# digital_clock_run4a.net
KiCad netlist of a schematic drawn in EasyEDA
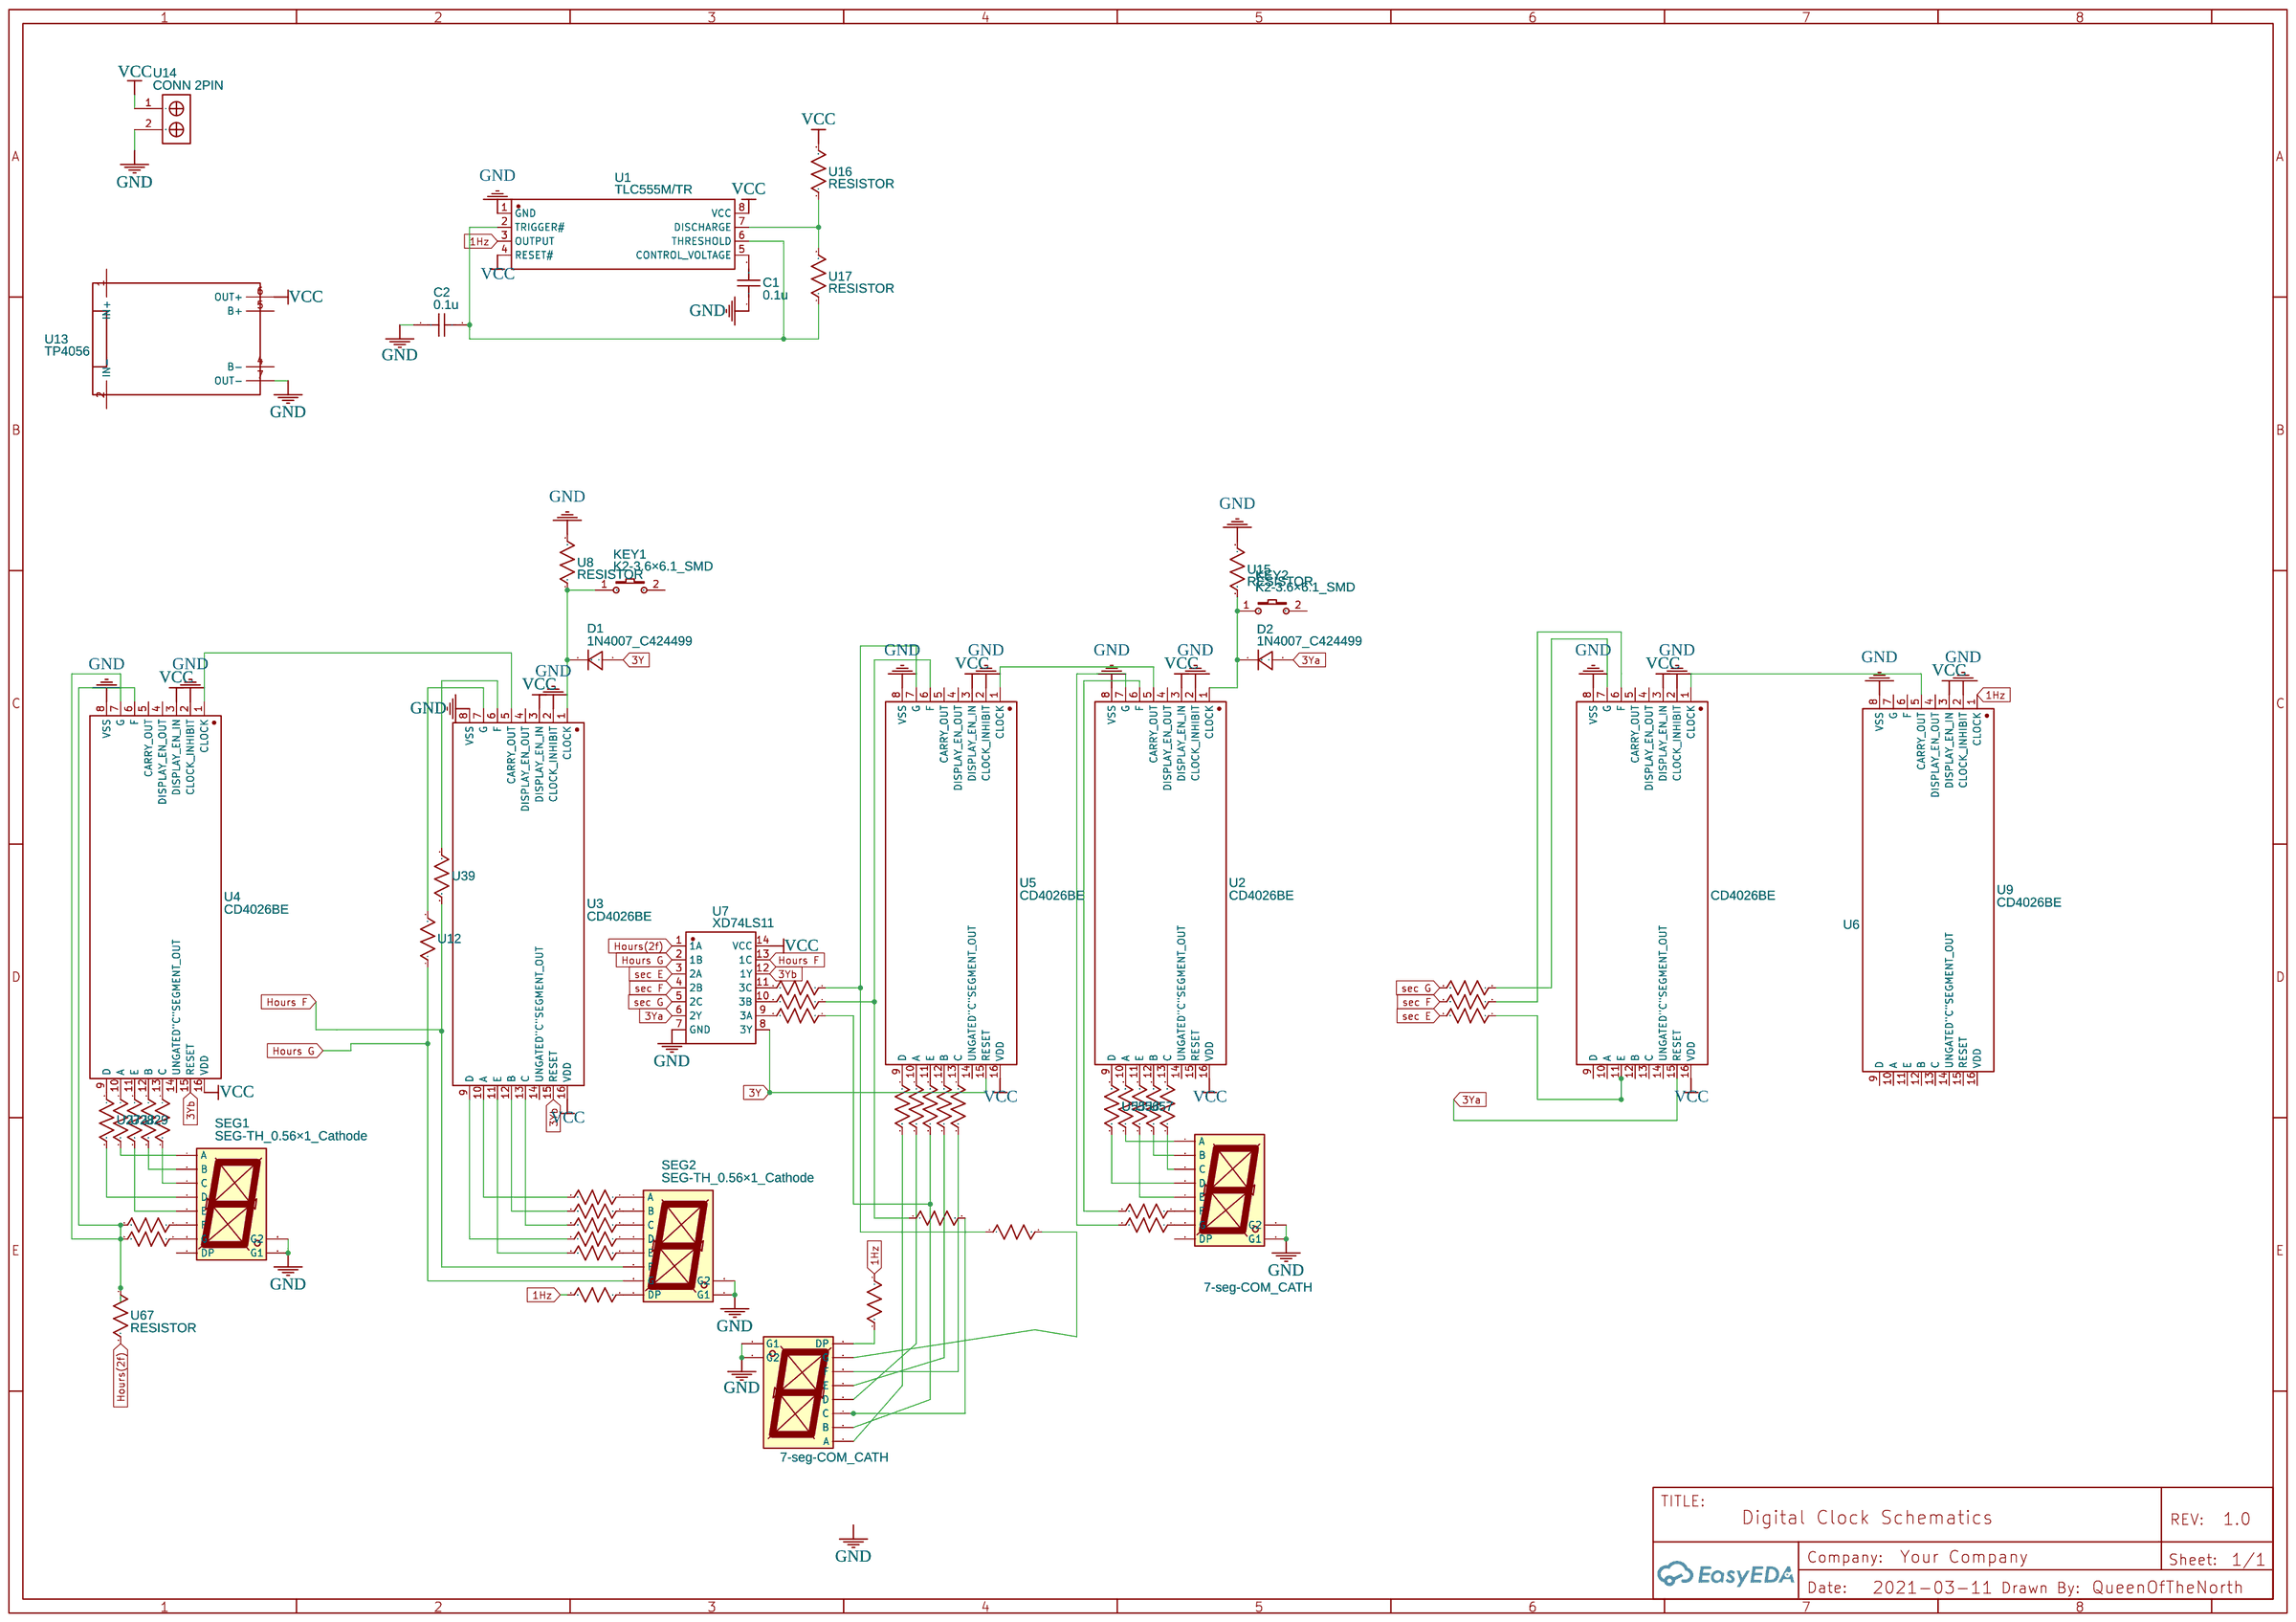
[diagram p0: schematic sheet]

(export (version "E")
  (design (tool "Eeschema 10.0.6"))
  (components
    (comp (ref "C1") (value "0.1u") (libsource (lib "") (part "C_0603_US_1")))
    (comp (ref "C2") (value "0.1u") (libsource (lib "") (part "C_0603_US")))
    (comp (ref "D1")
      (value "1N4007_C424499")
      (fields (field (name "BOM_Manufacturer Part") "1N4007") (field (name "BOM_Supplier Part") "C424499"))
      (libsource (lib "") (part "1N4007_C424499"))
    )
    (comp (ref "D2")
      (value "1N4007_C424499")
      (fields (field (name "BOM_Manufacturer Part") "1N4007") (field (name "BOM_Supplier Part") "C424499"))
      (libsource (lib "") (part "1N4007_C424499"))
    )
    (comp (ref "KEY1")
      (value "K2-3.6×6.1_SMD")
      (fields
        (field (name "BOM_Manufacturer Part") "K2-1107ST-A4SW-06")
        (field (name "BOM_Supplier Part") "C118141")
      )
      (libsource (lib "") (part "K2-3.6×6.1_SMD"))
    )
    (comp (ref "KEY2")
      (value "K2-3.6×6.1_SMD")
      (fields
        (field (name "BOM_Manufacturer Part") "K2-1107ST-A4SW-06")
        (field (name "BOM_Supplier Part") "C118141")
      )
      (libsource (lib "") (part "K2-3.6×6.1_SMD"))
    )
    (comp (ref "SEG1")
      (value "SEG-TH_0.56×1_Cathode")
      (fields (field (name "BOM_Supplier Part") "C8093"))
      (libsource (lib "") (part "SEG-TH_0.56×1_Cathode"))
    )
    (comp (ref "SEG2")
      (value "SEG-TH_0.56×1_Cathode")
      (fields (field (name "BOM_Supplier Part") "C8093"))
      (libsource (lib "") (part "SEG-TH_0.56×1_Cathode"))
    )
    (comp (ref "SEG3")
      (value "7-seg-COM_CATH")
      (fields (field (name "BOM_Supplier Part") "C8093"))
      (libsource (lib "") (part "SEG-TH_0.56×1_Cathode_1"))
    )
    (comp (ref "SEG4")
      (value "7-seg-COM_CATH")
      (fields (field (name "BOM_Supplier Part") "C8093"))
      (libsource (lib "") (part "SEG-TH_0.56×1_Cathode"))
    )
    (comp (ref "U1")
      (value "TLC555M/TR")
      (fields (field (name "BOM_Supplier Part") "C383061"))
      (libsource (lib "") (part "TLC555M/TR"))
    )
    (comp (ref "U2")
      (value "CD4026BE")
      (fields (field (name "BOM_Supplier Part") "C89909"))
      (libsource (lib "") (part "CD4026BE"))
    )
    (comp (ref "U3")
      (value "CD4026BE")
      (fields (field (name "BOM_Supplier Part") "C89909"))
      (libsource (lib "") (part "CD4026BE"))
    )
    (comp (ref "U4")
      (value "CD4026BE")
      (fields (field (name "BOM_Supplier Part") "C89909"))
      (libsource (lib "") (part "CD4026BE"))
    )
    (comp (ref "U5")
      (value "CD4026BE")
      (fields (field (name "BOM_Supplier Part") "C89909"))
      (libsource (lib "") (part "CD4026BE"))
    )
    (comp (ref "U6")
      (value "CD4026BE")
      (fields (field (name "BOM_Supplier Part") "C89909"))
      (libsource (lib "") (part "CD4026BE"))
    )
    (comp (ref "U7")
      (value "XD74LS11")
      (fields (field (name "BOM_Supplier Part") "C521167"))
      (libsource (lib "") (part "XD74LS11"))
    )
    (comp (ref "U8")
      (value "RESISTOR")
      (fields (field (name "BOM_Manufacturer Part") "0.4W 1% RESISTOR"))
      (libsource (lib "") (part "RESISTOR_1"))
    )
    (comp (ref "U9")
      (value "CD4026BE")
      (fields (field (name "BOM_Supplier Part") "C89909"))
      (libsource (lib "") (part "CD4026BE"))
    )
    (comp (ref "U10")
      (value "RESISTOR")
      (fields (field (name "BOM_Manufacturer Part") "0.4W 1% RESISTOR"))
      (libsource (lib "") (part "RESISTOR_7"))
    )
    (comp (ref "U11")
      (value "RESISTOR")
      (fields (field (name "BOM_Manufacturer Part") "0.4W 1% RESISTOR"))
      (libsource (lib "") (part "RESISTOR_2"))
    )
    (comp (ref "U12")
      (value "RESISTOR")
      (fields (field (name "BOM_Manufacturer Part") "0.4W 1% RESISTOR"))
      (libsource (lib "") (part "RESISTOR_5"))
    )
    (comp (ref "U13")
      (value "TP4056")
      (fields (field (name "BOM_Manufacturer Part") "TP4056-protect"))
      (libsource (lib "") (part "TP4056"))
    )
    (comp (ref "U14")
      (value "CONN 2PIN")
      (fields
        (field (name "BOM_Manufacturer Part") "Terminal Block")
        (field (name "BOM_Supplier Part") "undefined")
      )
      (libsource (lib "") (part "CONN 2PIN"))
    )
    (comp (ref "U15")
      (value "RESISTOR")
      (fields (field (name "BOM_Manufacturer Part") "0.4W 1% RESISTOR"))
      (libsource (lib "") (part "RESISTOR_1"))
    )
    (comp (ref "U16")
      (value "RESISTOR")
      (fields (field (name "BOM_Manufacturer Part") "0.4W 1% RESISTOR"))
      (libsource (lib "") (part "RESISTOR_1"))
    )
    (comp (ref "U17")
      (value "RESISTOR")
      (fields (field (name "BOM_Manufacturer Part") "0.4W 1% RESISTOR"))
      (libsource (lib "") (part "RESISTOR_1"))
    )
    (comp (ref "U18")
      (value "RESISTOR")
      (fields (field (name "BOM_Manufacturer Part") "0.4W 1% RESISTOR"))
      (libsource (lib "") (part "RESISTOR_2"))
    )
    (comp (ref "U19")
      (value "RESISTOR")
      (fields (field (name "BOM_Manufacturer Part") "0.4W 1% RESISTOR"))
      (libsource (lib "") (part "RESISTOR_2"))
    )
    (comp (ref "U20")
      (value "RESISTOR")
      (fields (field (name "BOM_Manufacturer Part") "0.4W 1% RESISTOR"))
      (libsource (lib "") (part "RESISTOR_2"))
    )
    (comp (ref "U21")
      (value "RESISTOR")
      (fields (field (name "BOM_Manufacturer Part") "0.4W 1% RESISTOR"))
      (libsource (lib "") (part "RESISTOR_2"))
    )
    (comp (ref "U22")
      (value "RESISTOR")
      (fields (field (name "BOM_Manufacturer Part") "0.4W 1% RESISTOR"))
      (libsource (lib "") (part "RESISTOR_2"))
    )
    (comp (ref "U25")
      (value "RESISTOR")
      (fields (field (name "BOM_Manufacturer Part") "0.4W 1% RESISTOR"))
      (libsource (lib "") (part "RESISTOR_2"))
    )
    (comp (ref "U26")
      (value "RESISTOR")
      (fields (field (name "BOM_Manufacturer Part") "0.4W 1% RESISTOR"))
      (libsource (lib "") (part "RESISTOR_2"))
    )
    (comp (ref "U27")
      (value "RESISTOR")
      (fields (field (name "BOM_Manufacturer Part") "0.4W 1% RESISTOR"))
      (libsource (lib "") (part "RESISTOR"))
    )
    (comp (ref "U28")
      (value "RESISTOR")
      (fields (field (name "BOM_Manufacturer Part") "0.4W 1% RESISTOR"))
      (libsource (lib "") (part "RESISTOR"))
    )
    (comp (ref "U29")
      (value "RESISTOR")
      (fields (field (name "BOM_Manufacturer Part") "0.4W 1% RESISTOR"))
      (libsource (lib "") (part "RESISTOR"))
    )
    (comp (ref "U30")
      (value "RESISTOR")
      (fields (field (name "BOM_Manufacturer Part") "0.4W 1% RESISTOR"))
      (libsource (lib "") (part "RESISTOR"))
    )
    (comp (ref "U31")
      (value "RESISTOR")
      (fields (field (name "BOM_Manufacturer Part") "0.4W 1% RESISTOR"))
      (libsource (lib "") (part "RESISTOR"))
    )
    (comp (ref "U32")
      (value "RESISTOR")
      (fields (field (name "BOM_Manufacturer Part") "0.4W 1% RESISTOR"))
      (libsource (lib "") (part "RESISTOR"))
    )
    (comp (ref "U33")
      (value "RESISTOR")
      (fields (field (name "BOM_Manufacturer Part") "0.4W 1% RESISTOR"))
      (libsource (lib "") (part "RESISTOR"))
    )
    (comp (ref "U34")
      (value "RESISTOR")
      (fields (field (name "BOM_Manufacturer Part") "0.4W 1% RESISTOR"))
      (libsource (lib "") (part "RESISTOR"))
    )
    (comp (ref "U35")
      (value "RESISTOR")
      (fields (field (name "BOM_Manufacturer Part") "0.4W 1% RESISTOR"))
      (libsource (lib "") (part "RESISTOR"))
    )
    (comp (ref "U36")
      (value "RESISTOR")
      (fields (field (name "BOM_Manufacturer Part") "0.4W 1% RESISTOR"))
      (libsource (lib "") (part "RESISTOR"))
    )
    (comp (ref "U37")
      (value "RESISTOR")
      (fields (field (name "BOM_Manufacturer Part") "0.4W 1% RESISTOR"))
      (libsource (lib "") (part "RESISTOR_3"))
    )
    (comp (ref "U38")
      (value "RESISTOR")
      (fields (field (name "BOM_Manufacturer Part") "0.4W 1% RESISTOR"))
      (libsource (lib "") (part "RESISTOR_3"))
    )
    (comp (ref "U39")
      (value "RESISTOR")
      (fields (field (name "BOM_Manufacturer Part") "0.4W 1% RESISTOR"))
      (libsource (lib "") (part "RESISTOR_5"))
    )
    (comp (ref "U52")
      (value "RESISTOR")
      (fields (field (name "BOM_Manufacturer Part") "0.4W 1% RESISTOR"))
      (libsource (lib "") (part "RESISTOR_2"))
    )
    (comp (ref "U53")
      (value "RESISTOR")
      (fields (field (name "BOM_Manufacturer Part") "0.4W 1% RESISTOR"))
      (libsource (lib "") (part "RESISTOR_2"))
    )
    (comp (ref "U54")
      (value "RESISTOR")
      (fields (field (name "BOM_Manufacturer Part") "0.4W 1% RESISTOR"))
      (libsource (lib "") (part "RESISTOR_2"))
    )
    (comp (ref "U55")
      (value "RESISTOR")
      (fields (field (name "BOM_Manufacturer Part") "0.4W 1% RESISTOR"))
      (libsource (lib "") (part "RESISTOR_1"))
    )
    (comp (ref "U56")
      (value "RESISTOR")
      (fields (field (name "BOM_Manufacturer Part") "0.4W 1% RESISTOR"))
      (libsource (lib "") (part "RESISTOR_1"))
    )
    (comp (ref "U57")
      (value "RESISTOR")
      (fields (field (name "BOM_Manufacturer Part") "0.4W 1% RESISTOR"))
      (libsource (lib "") (part "RESISTOR_1"))
    )
    (comp (ref "U58")
      (value "RESISTOR")
      (fields (field (name "BOM_Manufacturer Part") "0.4W 1% RESISTOR"))
      (libsource (lib "") (part "RESISTOR_1"))
    )
    (comp (ref "U59")
      (value "RESISTOR")
      (fields (field (name "BOM_Manufacturer Part") "0.4W 1% RESISTOR"))
      (libsource (lib "") (part "RESISTOR_1"))
    )
    (comp (ref "U60")
      (value "RESISTOR")
      (fields (field (name "BOM_Manufacturer Part") "0.4W 1% RESISTOR"))
      (libsource (lib "") (part "RESISTOR_2"))
    )
    (comp (ref "U61")
      (value "RESISTOR")
      (fields (field (name "BOM_Manufacturer Part") "0.4W 1% RESISTOR"))
      (libsource (lib "") (part "RESISTOR_2"))
    )
    (comp (ref "U62")
      (value "RESISTOR")
      (fields (field (name "BOM_Manufacturer Part") "0.4W 1% RESISTOR"))
      (libsource (lib "") (part "RESISTOR_4"))
    )
    (comp (ref "U63")
      (value "RESISTOR")
      (fields (field (name "BOM_Manufacturer Part") "0.4W 1% RESISTOR"))
      (libsource (lib "") (part "RESISTOR_4"))
    )
    (comp (ref "U64")
      (value "RESISTOR")
      (fields (field (name "BOM_Manufacturer Part") "0.4W 1% RESISTOR"))
      (libsource (lib "") (part "RESISTOR_4"))
    )
    (comp (ref "U67")
      (value "RESISTOR")
      (fields (field (name "BOM_Manufacturer Part") "0.4W 1% RESISTOR"))
      (libsource (lib "") (part "RESISTOR_6"))
    )
  )
  (nets
    (net (code "1") (name "1Hz") (class "Default")
      (node (ref "U1") (pin "3") (pinfunction "OUTPUT_3") (pintype "unspecified"))
      (node (ref "U10") (pin "1") (pinfunction "1_1") (pintype "unspecified"))
      (node (ref "U11") (pin "2") (pinfunction "2_2") (pintype "unspecified"))
      (node (ref "U9") (pin "1") (pinfunction "CLOCK_1") (pintype "unspecified"))
    )
    (net (code "2") (name "3Y") (class "Default")
      (node (ref "D1") (pin "2") (pinfunction "A_2") (pintype "unspecified"))
      (node (ref "U5") (pin "15") (pinfunction "RESET_15") (pintype "unspecified"))
      (node (ref "U7") (pin "8") (pinfunction "3Y_8") (pintype "unspecified"))
    )
    (net (code "3") (name "3Ya") (class "Default")
      (node (ref "D2") (pin "2") (pinfunction "A_2") (pintype "unspecified"))
      (node (ref "U6") (pin "15") (pinfunction "RESET_15") (pintype "unspecified"))
      (node (ref "U7") (pin "6") (pinfunction "2Y_6") (pintype "unspecified"))
    )
    (net (code "4") (name "3Yb") (class "Default")
      (node (ref "U3") (pin "15") (pinfunction "RESET_15") (pintype "unspecified"))
      (node (ref "U4") (pin "15") (pinfunction "RESET_15") (pintype "unspecified"))
      (node (ref "U7") (pin "12") (pinfunction "1Y_12") (pintype "unspecified"))
    )
    (net (code "5") (name "GND") (class "Default")
      (node (ref "C1") (pin "1") (pinfunction "1_1") (pintype "unspecified"))
      (node (ref "C2") (pin "1") (pinfunction "1_1") (pintype "unspecified"))
      (node (ref "SEG1") (pin "3") (pinfunction "G1_3") (pintype "unspecified"))
      (node (ref "SEG1") (pin "8") (pinfunction "G2_8") (pintype "unspecified"))
      (node (ref "SEG2") (pin "3") (pinfunction "G1_3") (pintype "unspecified"))
      (node (ref "SEG2") (pin "8") (pinfunction "G2_8") (pintype "unspecified"))
      (node (ref "SEG3") (pin "3") (pinfunction "G1_3") (pintype "unspecified"))
      (node (ref "SEG3") (pin "8") (pinfunction "G2_8") (pintype "unspecified"))
      (node (ref "SEG4") (pin "3") (pinfunction "G1_3") (pintype "unspecified"))
      (node (ref "SEG4") (pin "8") (pinfunction "G2_8") (pintype "unspecified"))
      (node (ref "U1") (pin "1") (pinfunction "GND_1") (pintype "unspecified"))
      (node (ref "U13") (pin "7") (pinfunction "OUT-_7") (pintype "unspecified"))
      (node (ref "U14") (pin "2") (pinfunction "2_2") (pintype "unspecified"))
      (node (ref "U15") (pin "2") (pinfunction "2_2") (pintype "unspecified"))
      (node (ref "U2") (pin "2") (pinfunction "CLOCK_INHIBIT_2") (pintype "unspecified"))
      (node (ref "U2") (pin "8") (pinfunction "VSS_8") (pintype "unspecified"))
      (node (ref "U3") (pin "2") (pinfunction "CLOCK_INHIBIT_2") (pintype "unspecified"))
      (node (ref "U3") (pin "8") (pinfunction "VSS_8") (pintype "unspecified"))
      (node (ref "U4") (pin "2") (pinfunction "CLOCK_INHIBIT_2") (pintype "unspecified"))
      (node (ref "U4") (pin "8") (pinfunction "VSS_8") (pintype "unspecified"))
      (node (ref "U5") (pin "2") (pinfunction "CLOCK_INHIBIT_2") (pintype "unspecified"))
      (node (ref "U5") (pin "8") (pinfunction "VSS_8") (pintype "unspecified"))
      (node (ref "U6") (pin "2") (pinfunction "CLOCK_INHIBIT_2") (pintype "unspecified"))
      (node (ref "U6") (pin "8") (pinfunction "VSS_8") (pintype "unspecified"))
      (node (ref "U7") (pin "7") (pinfunction "GND_7") (pintype "unspecified"))
      (node (ref "U8") (pin "2") (pinfunction "2_2") (pintype "unspecified"))
      (node (ref "U9") (pin "2") (pinfunction "CLOCK_INHIBIT_2") (pintype "unspecified"))
      (node (ref "U9") (pin "8") (pinfunction "VSS_8") (pintype "unspecified"))
    )
    (net (code "6") (name "Hours F") (class "Default")
      (node (ref "SEG2") (pin "9") (pinfunction "F_9") (pintype "unspecified"))
      (node (ref "U39") (pin "1") (pinfunction "1_1") (pintype "unspecified"))
      (node (ref "U7") (pin "13") (pinfunction "1C_13") (pintype "unspecified"))
    )
    (net (code "7") (name "Hours G") (class "Default")
      (node (ref "SEG2") (pin "10") (pinfunction "G_10") (pintype "unspecified"))
      (node (ref "U12") (pin "1") (pinfunction "1_1") (pintype "unspecified"))
      (node (ref "U7") (pin "2") (pinfunction "1B_2") (pintype "unspecified"))
    )
    (net (code "8") (name "Hours(2f)") (class "Default")
      (node (ref "U67") (pin "2") (pinfunction "2_2") (pintype "unspecified"))
      (node (ref "U7") (pin "1") (pinfunction "1A_1") (pintype "unspecified"))
    )
    (net (code "9") (name "Net-(D1-C)") (class "Default")
      (node (ref "D1") (pin "1") (pinfunction "C_1") (pintype "unspecified"))
      (node (ref "KEY1") (pin "1") (pinfunction "1_1") (pintype "unspecified"))
      (node (ref "U3") (pin "1") (pinfunction "CLOCK_1") (pintype "unspecified"))
      (node (ref "U8") (pin "1") (pinfunction "1_1") (pintype "unspecified"))
    )
    (net (code "10") (name "Net-(D2-C)") (class "Default")
      (node (ref "D2") (pin "1") (pinfunction "C_1") (pintype "unspecified"))
      (node (ref "KEY2") (pin "1") (pinfunction "1_1") (pintype "unspecified"))
      (node (ref "U15") (pin "1") (pinfunction "1_1") (pintype "unspecified"))
      (node (ref "U2") (pin "1") (pinfunction "CLOCK_1") (pintype "unspecified"))
    )
    (net (code "11") (name "Net-(SEG1-A)") (class "Default")
      (node (ref "SEG1") (pin "7") (pinfunction "A_7") (pintype "unspecified"))
      (node (ref "U28") (pin "2") (pinfunction "2_2") (pintype "unspecified"))
    )
    (net (code "12") (name "Net-(SEG1-B)") (class "Default")
      (node (ref "SEG1") (pin "6") (pinfunction "B_6") (pintype "unspecified"))
      (node (ref "U30") (pin "2") (pinfunction "2_2") (pintype "unspecified"))
    )
    (net (code "13") (name "Net-(SEG1-C)") (class "Default")
      (node (ref "SEG1") (pin "4") (pinfunction "C_4") (pintype "unspecified"))
      (node (ref "U31") (pin "2") (pinfunction "2_2") (pintype "unspecified"))
    )
    (net (code "14") (name "Net-(SEG1-D)") (class "Default")
      (node (ref "SEG1") (pin "2") (pinfunction "D_2") (pintype "unspecified"))
      (node (ref "U27") (pin "2") (pinfunction "2_2") (pintype "unspecified"))
    )
    (net (code "15") (name "Net-(SEG1-E)") (class "Default")
      (node (ref "SEG1") (pin "1") (pinfunction "E_1") (pintype "unspecified"))
      (node (ref "U29") (pin "2") (pinfunction "2_2") (pintype "unspecified"))
    )
    (net (code "16") (name "Net-(SEG1-F)") (class "Default")
      (node (ref "SEG1") (pin "9") (pinfunction "F_9") (pintype "unspecified"))
      (node (ref "U26") (pin "1") (pinfunction "1_1") (pintype "unspecified"))
    )
    (net (code "17") (name "Net-(SEG1-G)") (class "Default")
      (node (ref "SEG1") (pin "10") (pinfunction "G_10") (pintype "unspecified"))
      (node (ref "U25") (pin "1") (pinfunction "1_1") (pintype "unspecified"))
    )
    (net (code "18") (name "Net-(SEG2-A)") (class "Default")
      (node (ref "SEG2") (pin "7") (pinfunction "A_7") (pintype "unspecified"))
      (node (ref "U18") (pin "1") (pinfunction "1_1") (pintype "unspecified"))
    )
    (net (code "19") (name "Net-(SEG2-B)") (class "Default")
      (node (ref "SEG2") (pin "6") (pinfunction "B_6") (pintype "unspecified"))
      (node (ref "U19") (pin "1") (pinfunction "1_1") (pintype "unspecified"))
    )
    (net (code "20") (name "Net-(SEG2-C)") (class "Default")
      (node (ref "SEG2") (pin "4") (pinfunction "C_4") (pintype "unspecified"))
      (node (ref "U20") (pin "1") (pinfunction "1_1") (pintype "unspecified"))
    )
    (net (code "21") (name "Net-(SEG2-D)") (class "Default")
      (node (ref "SEG2") (pin "2") (pinfunction "D_2") (pintype "unspecified"))
      (node (ref "U21") (pin "1") (pinfunction "1_1") (pintype "unspecified"))
    )
    (net (code "22") (name "Net-(SEG2-DP)") (class "Default")
      (node (ref "SEG2") (pin "5") (pinfunction "DP_5") (pintype "unspecified"))
      (node (ref "U11") (pin "1") (pinfunction "1_1") (pintype "unspecified"))
    )
    (net (code "23") (name "Net-(SEG2-E)") (class "Default")
      (node (ref "SEG2") (pin "1") (pinfunction "E_1") (pintype "unspecified"))
      (node (ref "U22") (pin "1") (pinfunction "1_1") (pintype "unspecified"))
    )
    (net (code "24") (name "Net-(SEG3-A)") (class "Default")
      (node (ref "SEG3") (pin "7") (pinfunction "A_7") (pintype "unspecified"))
      (node (ref "U36") (pin "2") (pinfunction "2_2") (pintype "unspecified"))
    )
    (net (code "25") (name "Net-(SEG3-B)") (class "Default")
      (node (ref "SEG3") (pin "6") (pinfunction "B_6") (pintype "unspecified"))
      (node (ref "U34") (pin "2") (pinfunction "2_2") (pintype "unspecified"))
      (node (ref "U64") (pin "1") (pinfunction "1_1") (pintype "unspecified"))
    )
    (net (code "26") (name "Net-(SEG3-C)") (class "Default")
      (node (ref "SEG3") (pin "4") (pinfunction "C_4") (pintype "unspecified"))
      (node (ref "U37") (pin "2") (pinfunction "2_2") (pintype "unspecified"))
    )
    (net (code "27") (name "Net-(SEG3-D)") (class "Default")
      (node (ref "SEG3") (pin "2") (pinfunction "D_2") (pintype "unspecified"))
      (node (ref "U35") (pin "2") (pinfunction "2_2") (pintype "unspecified"))
    )
    (net (code "28") (name "Net-(SEG3-DP)") (class "Default")
      (node (ref "SEG3") (pin "5") (pinfunction "DP_5") (pintype "unspecified"))
      (node (ref "U10") (pin "2") (pinfunction "2_2") (pintype "unspecified"))
    )
    (net (code "29") (name "Net-(SEG3-E)") (class "Default")
      (node (ref "SEG3") (pin "1") (pinfunction "E_1") (pintype "unspecified"))
      (node (ref "U33") (pin "2") (pinfunction "2_2") (pintype "unspecified"))
    )
    (net (code "30") (name "Net-(SEG3-F)") (class "Default")
      (node (ref "SEG3") (pin "9") (pinfunction "F_9") (pintype "unspecified"))
      (node (ref "U32") (pin "2") (pinfunction "2_2") (pintype "unspecified"))
    )
    (net (code "31") (name "Net-(SEG3-G)") (class "Default")
      (node (ref "SEG3") (pin "10") (pinfunction "G_10") (pintype "unspecified"))
      (node (ref "U38") (pin "2") (pinfunction "2_2") (pintype "unspecified"))
    )
    (net (code "32") (name "Net-(SEG4-A)") (class "Default")
      (node (ref "SEG4") (pin "7") (pinfunction "A_7") (pintype "unspecified"))
      (node (ref "U56") (pin "1") (pinfunction "1_1") (pintype "unspecified"))
    )
    (net (code "33") (name "Net-(SEG4-B)") (class "Default")
      (node (ref "SEG4") (pin "6") (pinfunction "B_6") (pintype "unspecified"))
      (node (ref "U58") (pin "1") (pinfunction "1_1") (pintype "unspecified"))
    )
    (net (code "34") (name "Net-(SEG4-C)") (class "Default")
      (node (ref "SEG4") (pin "4") (pinfunction "C_4") (pintype "unspecified"))
      (node (ref "U59") (pin "1") (pinfunction "1_1") (pintype "unspecified"))
    )
    (net (code "35") (name "Net-(SEG4-D)") (class "Default")
      (node (ref "SEG4") (pin "2") (pinfunction "D_2") (pintype "unspecified"))
      (node (ref "U55") (pin "1") (pinfunction "1_1") (pintype "unspecified"))
    )
    (net (code "36") (name "Net-(SEG4-E)") (class "Default")
      (node (ref "SEG4") (pin "1") (pinfunction "E_1") (pintype "unspecified"))
      (node (ref "U57") (pin "1") (pinfunction "1_1") (pintype "unspecified"))
    )
    (net (code "37") (name "Net-(SEG4-F)") (class "Default")
      (node (ref "SEG4") (pin "9") (pinfunction "F_9") (pintype "unspecified"))
      (node (ref "U61") (pin "1") (pinfunction "1_1") (pintype "unspecified"))
    )
    (net (code "38") (name "Net-(SEG4-G)") (class "Default")
      (node (ref "SEG4") (pin "10") (pinfunction "G_10") (pintype "unspecified"))
      (node (ref "U60") (pin "1") (pinfunction "1_1") (pintype "unspecified"))
    )
    (net (code "39") (name "Net-(U1-CONTROL_VOLTAGE)") (class "Default")
      (node (ref "C1") (pin "2") (pinfunction "2_2") (pintype "unspecified"))
      (node (ref "U1") (pin "5") (pinfunction "CONTROL_VOLTAGE_5") (pintype "unspecified"))
    )
    (net (code "40") (name "Net-(U1-DISCHARGE)") (class "Default")
      (node (ref "U1") (pin "7") (pinfunction "DISCHARGE_7") (pintype "unspecified"))
      (node (ref "U16") (pin "1") (pinfunction "1_1") (pintype "unspecified"))
      (node (ref "U17") (pin "2") (pinfunction "2_2") (pintype "unspecified"))
    )
    (net (code "41") (name "Net-(U1-THRESHOLD)") (class "Default")
      (node (ref "C2") (pin "2") (pinfunction "2_2") (pintype "unspecified"))
      (node (ref "U1") (pin "2") (pinfunction "TRIGGER#_2") (pintype "unspecified"))
      (node (ref "U1") (pin "6") (pinfunction "THRESHOLD_6") (pintype "unspecified"))
      (node (ref "U17") (pin "1") (pinfunction "1_1") (pintype "unspecified"))
    )
    (net (code "42") (name "Net-(U2-A)") (class "Default")
      (node (ref "U2") (pin "10") (pinfunction "A_10") (pintype "unspecified"))
      (node (ref "U56") (pin "2") (pinfunction "2_2") (pintype "unspecified"))
    )
    (net (code "43") (name "Net-(U2-B)") (class "Default")
      (node (ref "U2") (pin "12") (pinfunction "B_12") (pintype "unspecified"))
      (node (ref "U58") (pin "2") (pinfunction "2_2") (pintype "unspecified"))
    )
    (net (code "44") (name "Net-(U2-C)") (class "Default")
      (node (ref "U2") (pin "13") (pinfunction "C_13") (pintype "unspecified"))
      (node (ref "U59") (pin "2") (pinfunction "2_2") (pintype "unspecified"))
    )
    (net (code "45") (name "Net-(U2-CARRY_OUT)") (class "Default")
      (node (ref "U2") (pin "5") (pinfunction "CARRY_OUT_5") (pintype "unspecified"))
      (node (ref "U5") (pin "1") (pinfunction "CLOCK_1") (pintype "unspecified"))
    )
    (net (code "46") (name "Net-(U2-D)") (class "Default")
      (node (ref "U2") (pin "9") (pinfunction "D_9") (pintype "unspecified"))
      (node (ref "U55") (pin "2") (pinfunction "2_2") (pintype "unspecified"))
    )
    (net (code "47") (name "Net-(U2-E)") (class "Default")
      (node (ref "U2") (pin "11") (pinfunction "E_11") (pintype "unspecified"))
      (node (ref "U57") (pin "2") (pinfunction "2_2") (pintype "unspecified"))
    )
    (net (code "48") (name "Net-(U2-F)") (class "Default")
      (node (ref "U2") (pin "6") (pinfunction "F_6") (pintype "unspecified"))
      (node (ref "U61") (pin "2") (pinfunction "2_2") (pintype "unspecified"))
    )
    (net (code "49") (name "Net-(U2-G)") (class "Default")
      (node (ref "U2") (pin "7") (pinfunction "G_7") (pintype "unspecified"))
      (node (ref "U60") (pin "2") (pinfunction "2_2") (pintype "unspecified"))
    )
    (net (code "50") (name "Net-(U3-A)") (class "Default")
      (node (ref "U18") (pin "2") (pinfunction "2_2") (pintype "unspecified"))
      (node (ref "U3") (pin "10") (pinfunction "A_10") (pintype "unspecified"))
    )
    (net (code "51") (name "Net-(U3-B)") (class "Default")
      (node (ref "U19") (pin "2") (pinfunction "2_2") (pintype "unspecified"))
      (node (ref "U3") (pin "12") (pinfunction "B_12") (pintype "unspecified"))
    )
    (net (code "52") (name "Net-(U3-C)") (class "Default")
      (node (ref "U20") (pin "2") (pinfunction "2_2") (pintype "unspecified"))
      (node (ref "U3") (pin "13") (pinfunction "C_13") (pintype "unspecified"))
    )
    (net (code "53") (name "Net-(U3-CARRY_OUT)") (class "Default")
      (node (ref "U3") (pin "5") (pinfunction "CARRY_OUT_5") (pintype "unspecified"))
      (node (ref "U4") (pin "1") (pinfunction "CLOCK_1") (pintype "unspecified"))
    )
    (net (code "54") (name "Net-(U3-D)") (class "Default")
      (node (ref "U21") (pin "2") (pinfunction "2_2") (pintype "unspecified"))
      (node (ref "U3") (pin "9") (pinfunction "D_9") (pintype "unspecified"))
    )
    (net (code "55") (name "Net-(U3-E)") (class "Default")
      (node (ref "U22") (pin "2") (pinfunction "2_2") (pintype "unspecified"))
      (node (ref "U3") (pin "11") (pinfunction "E_11") (pintype "unspecified"))
    )
    (net (code "56") (name "Net-(U3-F)") (class "Default")
      (node (ref "U3") (pin "6") (pinfunction "F_6") (pintype "unspecified"))
      (node (ref "U39") (pin "2") (pinfunction "2_2") (pintype "unspecified"))
    )
    (net (code "57") (name "Net-(U3-G)") (class "Default")
      (node (ref "U12") (pin "2") (pinfunction "2_2") (pintype "unspecified"))
      (node (ref "U3") (pin "7") (pinfunction "G_7") (pintype "unspecified"))
    )
    (net (code "58") (name "Net-(U4-A)") (class "Default")
      (node (ref "U28") (pin "1") (pinfunction "1_1") (pintype "unspecified"))
      (node (ref "U4") (pin "10") (pinfunction "A_10") (pintype "unspecified"))
    )
    (net (code "59") (name "Net-(U4-B)") (class "Default")
      (node (ref "U30") (pin "1") (pinfunction "1_1") (pintype "unspecified"))
      (node (ref "U4") (pin "12") (pinfunction "B_12") (pintype "unspecified"))
    )
    (net (code "60") (name "Net-(U4-C)") (class "Default")
      (node (ref "U31") (pin "1") (pinfunction "1_1") (pintype "unspecified"))
      (node (ref "U4") (pin "13") (pinfunction "C_13") (pintype "unspecified"))
    )
    (net (code "61") (name "Net-(U4-D)") (class "Default")
      (node (ref "U27") (pin "1") (pinfunction "1_1") (pintype "unspecified"))
      (node (ref "U4") (pin "9") (pinfunction "D_9") (pintype "unspecified"))
    )
    (net (code "62") (name "Net-(U4-E)") (class "Default")
      (node (ref "U29") (pin "1") (pinfunction "1_1") (pintype "unspecified"))
      (node (ref "U4") (pin "11") (pinfunction "E_11") (pintype "unspecified"))
    )
    (net (code "63") (name "Net-(U4-F)") (class "Default")
      (node (ref "U25") (pin "2") (pinfunction "2_2") (pintype "unspecified"))
      (node (ref "U26") (pin "2") (pinfunction "2_2") (pintype "unspecified"))
      (node (ref "U4") (pin "6") (pinfunction "F_6") (pintype "unspecified"))
      (node (ref "U4") (pin "7") (pinfunction "G_7") (pintype "unspecified"))
      (node (ref "U67") (pin "1") (pinfunction "1_1") (pintype "unspecified"))
    )
    (net (code "64") (name "Net-(U5-A)") (class "Default")
      (node (ref "U35") (pin "1") (pinfunction "1_1") (pintype "unspecified"))
      (node (ref "U5") (pin "10") (pinfunction "A_10") (pintype "unspecified"))
    )
    (net (code "65") (name "Net-(U5-B)") (class "Default")
      (node (ref "U33") (pin "1") (pinfunction "1_1") (pintype "unspecified"))
      (node (ref "U5") (pin "12") (pinfunction "B_12") (pintype "unspecified"))
    )
    (net (code "66") (name "Net-(U5-C)") (class "Default")
      (node (ref "U32") (pin "1") (pinfunction "1_1") (pintype "unspecified"))
      (node (ref "U5") (pin "13") (pinfunction "C_13") (pintype "unspecified"))
    )
    (net (code "67") (name "Net-(U5-D)") (class "Default")
      (node (ref "U36") (pin "1") (pinfunction "1_1") (pintype "unspecified"))
      (node (ref "U5") (pin "9") (pinfunction "D_9") (pintype "unspecified"))
    )
    (net (code "68") (name "Net-(U5-E)") (class "Default")
      (node (ref "U34") (pin "1") (pinfunction "1_1") (pintype "unspecified"))
      (node (ref "U5") (pin "11") (pinfunction "E_11") (pintype "unspecified"))
    )
    (net (code "69") (name "Net-(U5-F)") (class "Default")
      (node (ref "U37") (pin "1") (pinfunction "1_1") (pintype "unspecified"))
      (node (ref "U5") (pin "6") (pinfunction "F_6") (pintype "unspecified"))
      (node (ref "U63") (pin "1") (pinfunction "1_1") (pintype "unspecified"))
    )
    (net (code "70") (name "Net-(U5-G)") (class "Default")
      (node (ref "U38") (pin "1") (pinfunction "1_1") (pintype "unspecified"))
      (node (ref "U5") (pin "7") (pinfunction "G_7") (pintype "unspecified"))
      (node (ref "U62") (pin "1") (pinfunction "1_1") (pintype "unspecified"))
    )
    (net (code "71") (name "Net-(U6-CLOCK)") (class "Default")
      (node (ref "U6") (pin "1") (pinfunction "CLOCK_1") (pintype "unspecified"))
      (node (ref "U9") (pin "5") (pinfunction "CARRY_OUT_5") (pintype "unspecified"))
    )
    (net (code "72") (name "Net-(U6-E)") (class "Default")
      (node (ref "U52") (pin "1") (pinfunction "1_1") (pintype "unspecified"))
      (node (ref "U6") (pin "11") (pinfunction "E_11") (pintype "unspecified"))
    )
    (net (code "73") (name "Net-(U6-F)") (class "Default")
      (node (ref "U53") (pin "1") (pinfunction "1_1") (pintype "unspecified"))
      (node (ref "U6") (pin "6") (pinfunction "F_6") (pintype "unspecified"))
    )
    (net (code "74") (name "Net-(U6-G)") (class "Default")
      (node (ref "U54") (pin "1") (pinfunction "1_1") (pintype "unspecified"))
      (node (ref "U6") (pin "7") (pinfunction "G_7") (pintype "unspecified"))
    )
    (net (code "75") (name "Net-(U7-3A)") (class "Default")
      (node (ref "U64") (pin "2") (pinfunction "2_2") (pintype "unspecified"))
      (node (ref "U7") (pin "9") (pinfunction "3A_9") (pintype "unspecified"))
    )
    (net (code "76") (name "Net-(U7-3B)") (class "Default")
      (node (ref "U63") (pin "2") (pinfunction "2_2") (pintype "unspecified"))
      (node (ref "U7") (pin "10") (pinfunction "3B_10") (pintype "unspecified"))
    )
    (net (code "77") (name "Net-(U7-3C)") (class "Default")
      (node (ref "U62") (pin "2") (pinfunction "2_2") (pintype "unspecified"))
      (node (ref "U7") (pin "11") (pinfunction "3C_11") (pintype "unspecified"))
    )
    (net (code "78") (name "VCC") (class "Default")
      (node (ref "U1") (pin "4") (pinfunction "RESET#_4") (pintype "unspecified"))
      (node (ref "U1") (pin "8") (pinfunction "VCC_8") (pintype "unspecified"))
      (node (ref "U13") (pin "6") (pinfunction "OUT+_6") (pintype "unspecified"))
      (node (ref "U14") (pin "1") (pinfunction "1_1") (pintype "unspecified"))
      (node (ref "U16") (pin "2") (pinfunction "2_2") (pintype "unspecified"))
      (node (ref "U2") (pin "16") (pinfunction "VDD_16") (pintype "unspecified"))
      (node (ref "U2") (pin "3") (pinfunction "DISPLAY_EN_IN_3") (pintype "unspecified"))
      (node (ref "U3") (pin "16") (pinfunction "VDD_16") (pintype "unspecified"))
      (node (ref "U3") (pin "3") (pinfunction "DISPLAY_EN_IN_3") (pintype "unspecified"))
      (node (ref "U4") (pin "16") (pinfunction "VDD_16") (pintype "unspecified"))
      (node (ref "U4") (pin "3") (pinfunction "DISPLAY_EN_IN_3") (pintype "unspecified"))
      (node (ref "U5") (pin "16") (pinfunction "VDD_16") (pintype "unspecified"))
      (node (ref "U5") (pin "3") (pinfunction "DISPLAY_EN_IN_3") (pintype "unspecified"))
      (node (ref "U6") (pin "16") (pinfunction "VDD_16") (pintype "unspecified"))
      (node (ref "U6") (pin "3") (pinfunction "DISPLAY_EN_IN_3") (pintype "unspecified"))
      (node (ref "U7") (pin "14") (pinfunction "VCC_14") (pintype "unspecified"))
      (node (ref "U9") (pin "3") (pinfunction "DISPLAY_EN_IN_3") (pintype "unspecified"))
    )
    (net (code "79") (name "sec E") (class "Default")
      (node (ref "U52") (pin "2") (pinfunction "2_2") (pintype "unspecified"))
      (node (ref "U7") (pin "3") (pinfunction "2A_3") (pintype "unspecified"))
    )
    (net (code "80") (name "sec F") (class "Default")
      (node (ref "U53") (pin "2") (pinfunction "2_2") (pintype "unspecified"))
      (node (ref "U7") (pin "4") (pinfunction "2B_4") (pintype "unspecified"))
    )
    (net (code "81") (name "sec G") (class "Default")
      (node (ref "U54") (pin "2") (pinfunction "2_2") (pintype "unspecified"))
      (node (ref "U7") (pin "5") (pinfunction "2C_5") (pintype "unspecified"))
    )
    (net (code "82") (name "unconnected-(KEY1-Pad2)") (class "Default")
      (node (ref "KEY1") (pin "2") (pinfunction "2_2") (pintype "unspecified"))
    )
    (net (code "83") (name "unconnected-(KEY2-Pad2)") (class "Default")
      (node (ref "KEY2") (pin "2") (pinfunction "2_2") (pintype "unspecified"))
    )
    (net (code "84") (name "unconnected-(SEG1-DP-Pad5)") (class "Default")
      (node (ref "SEG1") (pin "5") (pinfunction "DP_5") (pintype "unspecified"))
    )
    (net (code "85") (name "unconnected-(SEG4-DP-Pad5)") (class "Default")
      (node (ref "SEG4") (pin "5") (pinfunction "DP_5") (pintype "unspecified"))
    )
    (net (code "86") (name "unconnected-(U2-DISPLAY_EN_OUT-Pad4)") (class "Default")
      (node (ref "U2") (pin "4") (pinfunction "DISPLAY_EN_OUT_4") (pintype "unspecified"))
    )
    (net (code "87") (name "unconnected-(U2-RESET-Pad15)") (class "Default")
      (node (ref "U2") (pin "15") (pinfunction "RESET_15") (pintype "unspecified"))
    )
    (net (code "88") (name "unconnected-(U2-UNGATED\"C\"SEGMENT_OUT-Pad14)") (class "Default")
      (node (ref "U2") (pin "14") (pinfunction "UNGATED\"C\"SEGMENT_OUT_14") (pintype "unspecified"))
    )
    (net (code "89") (name "unconnected-(U3-DISPLAY_EN_OUT-Pad4)") (class "Default")
      (node (ref "U3") (pin "4") (pinfunction "DISPLAY_EN_OUT_4") (pintype "unspecified"))
    )
    (net (code "90") (name "unconnected-(U3-UNGATED\"C\"SEGMENT_OUT-Pad14)") (class "Default")
      (node (ref "U3") (pin "14") (pinfunction "UNGATED\"C\"SEGMENT_OUT_14") (pintype "unspecified"))
    )
    (net (code "91") (name "unconnected-(U4-CARRY_OUT-Pad5)") (class "Default")
      (node (ref "U4") (pin "5") (pinfunction "CARRY_OUT_5") (pintype "unspecified"))
    )
    (net (code "92") (name "unconnected-(U4-DISPLAY_EN_OUT-Pad4)") (class "Default")
      (node (ref "U4") (pin "4") (pinfunction "DISPLAY_EN_OUT_4") (pintype "unspecified"))
    )
    (net (code "93") (name "unconnected-(U4-UNGATED\"C\"SEGMENT_OUT-Pad14)") (class "Default")
      (node (ref "U4") (pin "14") (pinfunction "UNGATED\"C\"SEGMENT_OUT_14") (pintype "unspecified"))
    )
    (net (code "94") (name "unconnected-(U5-CARRY_OUT-Pad5)") (class "Default")
      (node (ref "U5") (pin "5") (pinfunction "CARRY_OUT_5") (pintype "unspecified"))
    )
    (net (code "95") (name "unconnected-(U5-DISPLAY_EN_OUT-Pad4)") (class "Default")
      (node (ref "U5") (pin "4") (pinfunction "DISPLAY_EN_OUT_4") (pintype "unspecified"))
    )
    (net (code "96") (name "unconnected-(U5-UNGATED\"C\"SEGMENT_OUT-Pad14)") (class "Default")
      (node (ref "U5") (pin "14") (pinfunction "UNGATED\"C\"SEGMENT_OUT_14") (pintype "unspecified"))
    )
    (net (code "97") (name "unconnected-(U6-A-Pad10)") (class "Default")
      (node (ref "U6") (pin "10") (pinfunction "A_10") (pintype "unspecified"))
    )
    (net (code "98") (name "unconnected-(U6-B-Pad12)") (class "Default")
      (node (ref "U6") (pin "12") (pinfunction "B_12") (pintype "unspecified"))
    )
    (net (code "99") (name "unconnected-(U6-C-Pad13)") (class "Default")
      (node (ref "U6") (pin "13") (pinfunction "C_13") (pintype "unspecified"))
    )
    (net (code "100") (name "unconnected-(U6-CARRY_OUT-Pad5)") (class "Default")
      (node (ref "U6") (pin "5") (pinfunction "CARRY_OUT_5") (pintype "unspecified"))
    )
    (net (code "101") (name "unconnected-(U6-D-Pad9)") (class "Default")
      (node (ref "U6") (pin "9") (pinfunction "D_9") (pintype "unspecified"))
    )
    (net (code "102") (name "unconnected-(U6-DISPLAY_EN_OUT-Pad4)") (class "Default")
      (node (ref "U6") (pin "4") (pinfunction "DISPLAY_EN_OUT_4") (pintype "unspecified"))
    )
    (net (code "103") (name "unconnected-(U6-UNGATED\"C\"SEGMENT_OUT-Pad14)") (class "Default")
      (node (ref "U6") (pin "14") (pinfunction "UNGATED\"C\"SEGMENT_OUT_14") (pintype "unspecified"))
    )
    (net (code "104") (name "unconnected-(U9-A-Pad10)") (class "Default")
      (node (ref "U9") (pin "10") (pinfunction "A_10") (pintype "unspecified"))
    )
    (net (code "105") (name "unconnected-(U9-B-Pad12)") (class "Default")
      (node (ref "U9") (pin "12") (pinfunction "B_12") (pintype "unspecified"))
    )
    (net (code "106") (name "unconnected-(U9-C-Pad13)") (class "Default")
      (node (ref "U9") (pin "13") (pinfunction "C_13") (pintype "unspecified"))
    )
    (net (code "107") (name "unconnected-(U9-D-Pad9)") (class "Default")
      (node (ref "U9") (pin "9") (pinfunction "D_9") (pintype "unspecified"))
    )
    (net (code "108") (name "unconnected-(U9-DISPLAY_EN_OUT-Pad4)") (class "Default")
      (node (ref "U9") (pin "4") (pinfunction "DISPLAY_EN_OUT_4") (pintype "unspecified"))
    )
    (net (code "109") (name "unconnected-(U9-E-Pad11)") (class "Default")
      (node (ref "U9") (pin "11") (pinfunction "E_11") (pintype "unspecified"))
    )
    (net (code "110") (name "unconnected-(U9-F-Pad6)") (class "Default")
      (node (ref "U9") (pin "6") (pinfunction "F_6") (pintype "unspecified"))
    )
    (net (code "111") (name "unconnected-(U9-G-Pad7)") (class "Default")
      (node (ref "U9") (pin "7") (pinfunction "G_7") (pintype "unspecified"))
    )
    (net (code "112") (name "unconnected-(U9-RESET-Pad15)") (class "Default")
      (node (ref "U9") (pin "15") (pinfunction "RESET_15") (pintype "unspecified"))
    )
    (net (code "113") (name "unconnected-(U9-UNGATED\"C\"SEGMENT_OUT-Pad14)") (class "Default")
      (node (ref "U9") (pin "14") (pinfunction "UNGATED\"C\"SEGMENT_OUT_14") (pintype "unspecified"))
    )
    (net (code "114") (name "unconnected-(U9-VDD-Pad16)") (class "Default")
      (node (ref "U9") (pin "16") (pinfunction "VDD_16") (pintype "unspecified"))
    )
    (net (code "115") (name "unconnected-(U13-B+-Pad5)") (class "Default")
      (node (ref "U13") (pin "5") (pinfunction "B+_5") (pintype "unspecified"))
    )
    (net (code "116") (name "unconnected-(U13-B--Pad4)") (class "Default")
      (node (ref "U13") (pin "4") (pinfunction "B-_4") (pintype "unspecified"))
    )
    (net (code "117") (name "unconnected-(U13-IN+-Pad1)") (class "Default")
      (node (ref "U13") (pin "1") (pinfunction "IN+_1") (pintype "unspecified"))
    )
    (net (code "118") (name "unconnected-(U13-IN--Pad2)") (class "Default")
      (node (ref "U13") (pin "2") (pinfunction "IN-_2") (pintype "unspecified"))
    )
  )
)
